# 05-Core_Connector.net
KiCad netlist of a schematic drawn in Altium Designer
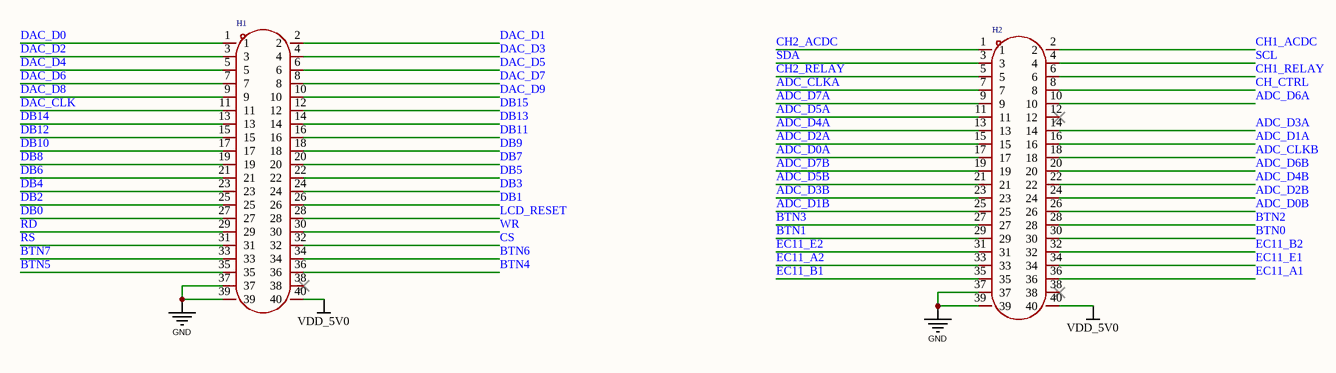
[diagram p0: 05-Core Connector.schdoc]

(export (version "E")
  (design (tool "Eeschema 10.0.6"))
  (components
    (comp (ref "H1")
      (value "12251220ANG0S115001")
      (footprint "HDR-TH_40P-P2.54-V-M-R2-C20-S2.54")
      (fields (field (name "MANUFACTURER") "JILN(锦凌)"))
      (libsource (lib "altium-import") (part "root_0_12251220ANG0S115001_"))
    )
    (comp (ref "H2")
      (value "12251220ANG0S115001")
      (footprint "HDR-TH_40P-P2.54-V-M-R2-C20-S2.54")
      (fields (field (name "MANUFACTURER") "JILN(锦凌)"))
      (libsource (lib "altium-import") (part "root_0_12251220ANG0S115001_"))
    )
  )
  (nets
    (net (code "1") (name "/ADC_CLKA") (class "Default")
      (node (ref "H2") (pin "7") (pinfunction "7_7") (pintype "passive"))
    )
    (net (code "2") (name "/ADC_CLKB") (class "Default")
      (node (ref "H2") (pin "18") (pinfunction "18_18") (pintype "passive"))
    )
    (net (code "3") (name "/ADC_D0A") (class "Default")
      (node (ref "H2") (pin "17") (pinfunction "17_17") (pintype "passive"))
    )
    (net (code "4") (name "/ADC_D0B") (class "Default")
      (node (ref "H2") (pin "26") (pinfunction "26_26") (pintype "passive"))
    )
    (net (code "5") (name "/ADC_D1A") (class "Default")
      (node (ref "H2") (pin "16") (pinfunction "16_16") (pintype "passive"))
    )
    (net (code "6") (name "/ADC_D1B") (class "Default")
      (node (ref "H2") (pin "25") (pinfunction "25_25") (pintype "passive"))
    )
    (net (code "7") (name "/ADC_D2A") (class "Default")
      (node (ref "H2") (pin "15") (pinfunction "15_15") (pintype "passive"))
    )
    (net (code "8") (name "/ADC_D2B") (class "Default")
      (node (ref "H2") (pin "24") (pinfunction "24_24") (pintype "passive"))
    )
    (net (code "9") (name "/ADC_D3A") (class "Default")
      (node (ref "H2") (pin "14") (pinfunction "14_14") (pintype "passive"))
    )
    (net (code "10") (name "/ADC_D3B") (class "Default")
      (node (ref "H2") (pin "23") (pinfunction "23_23") (pintype "passive"))
    )
    (net (code "11") (name "/ADC_D4A") (class "Default")
      (node (ref "H2") (pin "13") (pinfunction "13_13") (pintype "passive"))
    )
    (net (code "12") (name "/ADC_D4B") (class "Default")
      (node (ref "H2") (pin "22") (pinfunction "22_22") (pintype "passive"))
    )
    (net (code "13") (name "/ADC_D5A") (class "Default")
      (node (ref "H2") (pin "11") (pinfunction "11_11") (pintype "passive"))
    )
    (net (code "14") (name "/ADC_D5B") (class "Default")
      (node (ref "H2") (pin "21") (pinfunction "21_21") (pintype "passive"))
    )
    (net (code "15") (name "/ADC_D6A") (class "Default")
      (node (ref "H2") (pin "10") (pinfunction "10_10") (pintype "passive"))
    )
    (net (code "16") (name "/ADC_D6B") (class "Default")
      (node (ref "H2") (pin "20") (pinfunction "20_20") (pintype "passive"))
    )
    (net (code "17") (name "/ADC_D7A") (class "Default")
      (node (ref "H2") (pin "9") (pinfunction "9_9") (pintype "passive"))
    )
    (net (code "18") (name "/ADC_D7B") (class "Default")
      (node (ref "H2") (pin "19") (pinfunction "19_19") (pintype "passive"))
    )
    (net (code "19") (name "/BTN0") (class "Default")
      (node (ref "H2") (pin "30") (pinfunction "30_30") (pintype "passive"))
    )
    (net (code "20") (name "/BTN1") (class "Default")
      (node (ref "H2") (pin "29") (pinfunction "29_29") (pintype "passive"))
    )
    (net (code "21") (name "/BTN2") (class "Default")
      (node (ref "H2") (pin "28") (pinfunction "28_28") (pintype "passive"))
    )
    (net (code "22") (name "/BTN3") (class "Default")
      (node (ref "H2") (pin "27") (pinfunction "27_27") (pintype "passive"))
    )
    (net (code "23") (name "/BTN4") (class "Default")
      (node (ref "H1") (pin "36") (pinfunction "36_36") (pintype "passive"))
    )
    (net (code "24") (name "/BTN5") (class "Default")
      (node (ref "H1") (pin "35") (pinfunction "35_35") (pintype "passive"))
    )
    (net (code "25") (name "/BTN6") (class "Default")
      (node (ref "H1") (pin "34") (pinfunction "34_34") (pintype "passive"))
    )
    (net (code "26") (name "/BTN7") (class "Default")
      (node (ref "H1") (pin "33") (pinfunction "33_33") (pintype "passive"))
    )
    (net (code "27") (name "/CH1_ACDC") (class "Default")
      (node (ref "H2") (pin "2") (pinfunction "2_2") (pintype "passive"))
    )
    (net (code "28") (name "/CH1_RELAY") (class "Default")
      (node (ref "H2") (pin "6") (pinfunction "6_6") (pintype "passive"))
    )
    (net (code "29") (name "/CH2_ACDC") (class "Default")
      (node (ref "H2") (pin "1") (pinfunction "1_1") (pintype "passive"))
    )
    (net (code "30") (name "/CH2_RELAY") (class "Default")
      (node (ref "H2") (pin "5") (pinfunction "5_5") (pintype "passive"))
    )
    (net (code "31") (name "/CH_CTRL") (class "Default")
      (node (ref "H2") (pin "8") (pinfunction "8_8") (pintype "passive"))
    )
    (net (code "32") (name "/CS") (class "Default")
      (node (ref "H1") (pin "32") (pinfunction "32_32") (pintype "passive"))
    )
    (net (code "33") (name "/DAC_CLK") (class "Default")
      (node (ref "H1") (pin "11") (pinfunction "11_11") (pintype "passive"))
    )
    (net (code "34") (name "/DAC_D0") (class "Default")
      (node (ref "H1") (pin "1") (pinfunction "1_1") (pintype "passive"))
    )
    (net (code "35") (name "/DAC_D1") (class "Default")
      (node (ref "H1") (pin "2") (pinfunction "2_2") (pintype "passive"))
    )
    (net (code "36") (name "/DAC_D2") (class "Default")
      (node (ref "H1") (pin "3") (pinfunction "3_3") (pintype "passive"))
    )
    (net (code "37") (name "/DAC_D3") (class "Default")
      (node (ref "H1") (pin "4") (pinfunction "4_4") (pintype "passive"))
    )
    (net (code "38") (name "/DAC_D4") (class "Default")
      (node (ref "H1") (pin "5") (pinfunction "5_5") (pintype "passive"))
    )
    (net (code "39") (name "/DAC_D5") (class "Default")
      (node (ref "H1") (pin "6") (pinfunction "6_6") (pintype "passive"))
    )
    (net (code "40") (name "/DAC_D6") (class "Default")
      (node (ref "H1") (pin "7") (pinfunction "7_7") (pintype "passive"))
    )
    (net (code "41") (name "/DAC_D7") (class "Default")
      (node (ref "H1") (pin "8") (pinfunction "8_8") (pintype "passive"))
    )
    (net (code "42") (name "/DAC_D8") (class "Default")
      (node (ref "H1") (pin "9") (pinfunction "9_9") (pintype "passive"))
    )
    (net (code "43") (name "/DAC_D9") (class "Default")
      (node (ref "H1") (pin "10") (pinfunction "10_10") (pintype "passive"))
    )
    (net (code "44") (name "/DB0") (class "Default")
      (node (ref "H1") (pin "27") (pinfunction "27_27") (pintype "passive"))
    )
    (net (code "45") (name "/DB1") (class "Default")
      (node (ref "H1") (pin "26") (pinfunction "26_26") (pintype "passive"))
    )
    (net (code "46") (name "/DB2") (class "Default")
      (node (ref "H1") (pin "25") (pinfunction "25_25") (pintype "passive"))
    )
    (net (code "47") (name "/DB3") (class "Default")
      (node (ref "H1") (pin "24") (pinfunction "24_24") (pintype "passive"))
    )
    (net (code "48") (name "/DB4") (class "Default")
      (node (ref "H1") (pin "23") (pinfunction "23_23") (pintype "passive"))
    )
    (net (code "49") (name "/DB5") (class "Default")
      (node (ref "H1") (pin "22") (pinfunction "22_22") (pintype "passive"))
    )
    (net (code "50") (name "/DB6") (class "Default")
      (node (ref "H1") (pin "21") (pinfunction "21_21") (pintype "passive"))
    )
    (net (code "51") (name "/DB7") (class "Default")
      (node (ref "H1") (pin "20") (pinfunction "20_20") (pintype "passive"))
    )
    (net (code "52") (name "/DB8") (class "Default")
      (node (ref "H1") (pin "19") (pinfunction "19_19") (pintype "passive"))
    )
    (net (code "53") (name "/DB9") (class "Default")
      (node (ref "H1") (pin "18") (pinfunction "18_18") (pintype "passive"))
    )
    (net (code "54") (name "/DB10") (class "Default")
      (node (ref "H1") (pin "17") (pinfunction "17_17") (pintype "passive"))
    )
    (net (code "55") (name "/DB11") (class "Default")
      (node (ref "H1") (pin "16") (pinfunction "16_16") (pintype "passive"))
    )
    (net (code "56") (name "/DB12") (class "Default")
      (node (ref "H1") (pin "15") (pinfunction "15_15") (pintype "passive"))
    )
    (net (code "57") (name "/DB13") (class "Default")
      (node (ref "H1") (pin "14") (pinfunction "14_14") (pintype "passive"))
    )
    (net (code "58") (name "/DB14") (class "Default")
      (node (ref "H1") (pin "13") (pinfunction "13_13") (pintype "passive"))
    )
    (net (code "59") (name "/DB15") (class "Default")
      (node (ref "H1") (pin "12") (pinfunction "12_12") (pintype "passive"))
    )
    (net (code "60") (name "/EC11_A1") (class "Default")
      (node (ref "H2") (pin "36") (pinfunction "36_36") (pintype "passive"))
    )
    (net (code "61") (name "/EC11_A2") (class "Default")
      (node (ref "H2") (pin "33") (pinfunction "33_33") (pintype "passive"))
    )
    (net (code "62") (name "/EC11_B1") (class "Default")
      (node (ref "H2") (pin "35") (pinfunction "35_35") (pintype "passive"))
    )
    (net (code "63") (name "/EC11_B2") (class "Default")
      (node (ref "H2") (pin "32") (pinfunction "32_32") (pintype "passive"))
    )
    (net (code "64") (name "/EC11_E1") (class "Default")
      (node (ref "H2") (pin "34") (pinfunction "34_34") (pintype "passive"))
    )
    (net (code "65") (name "/EC11_E2") (class "Default")
      (node (ref "H2") (pin "31") (pinfunction "31_31") (pintype "passive"))
    )
    (net (code "66") (name "/LCD_RESET") (class "Default")
      (node (ref "H1") (pin "28") (pinfunction "28_28") (pintype "passive"))
    )
    (net (code "67") (name "/RD") (class "Default")
      (node (ref "H1") (pin "29") (pinfunction "29_29") (pintype "passive"))
    )
    (net (code "68") (name "/RS") (class "Default")
      (node (ref "H1") (pin "31") (pinfunction "31_31") (pintype "passive"))
    )
    (net (code "69") (name "/SCL") (class "Default")
      (node (ref "H2") (pin "4") (pinfunction "4_4") (pintype "passive"))
    )
    (net (code "70") (name "/SDA") (class "Default")
      (node (ref "H2") (pin "3") (pinfunction "3_3") (pintype "passive"))
    )
    (net (code "71") (name "/WR") (class "Default")
      (node (ref "H1") (pin "30") (pinfunction "30_30") (pintype "passive"))
    )
    (net (code "72") (name "GND") (class "Default")
      (node (ref "H1") (pin "37") (pinfunction "37_37") (pintype "passive"))
      (node (ref "H1") (pin "39") (pinfunction "39_39") (pintype "passive"))
      (node (ref "H2") (pin "37") (pinfunction "37_37") (pintype "passive"))
      (node (ref "H2") (pin "39") (pinfunction "39_39") (pintype "passive"))
    )
    (net (code "73") (name "VDD_5V0") (class "Default")
      (node (ref "H1") (pin "40") (pinfunction "40_40") (pintype "passive"))
      (node (ref "H2") (pin "40") (pinfunction "40_40") (pintype "passive"))
    )
    (net (code "74") (name "unconnected-(H1-Pad38)") (class "Default")
      (node (ref "H1") (pin "38") (pinfunction "38_38") (pintype "passive+no_connect"))
    )
    (net (code "75") (name "unconnected-(H2-Pad12)") (class "Default")
      (node (ref "H2") (pin "12") (pinfunction "12_12") (pintype "passive+no_connect"))
    )
    (net (code "76") (name "unconnected-(H2-Pad38)") (class "Default")
      (node (ref "H2") (pin "38") (pinfunction "38_38") (pintype "passive+no_connect"))
    )
  )
)
